# 5V_1A_Max.net
KiCad netlist of a schematic drawn in Altium Designer
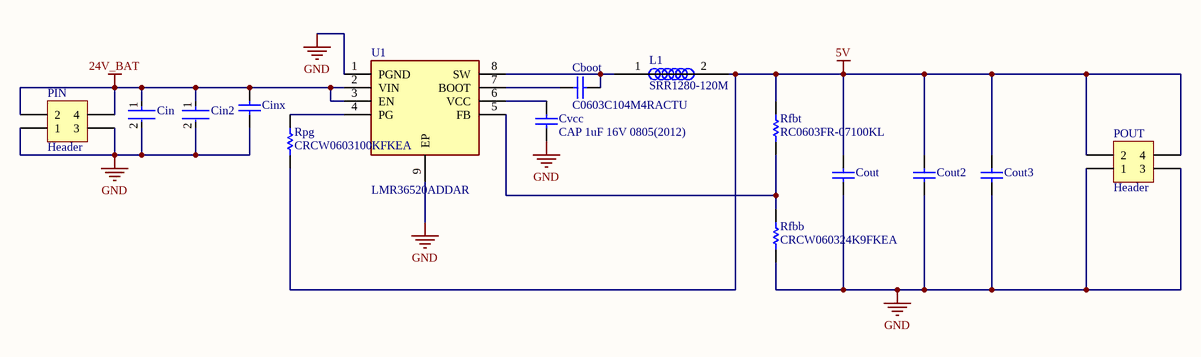
[diagram p0: 5V_1A_Max.SchDoc]

(export (version "E")
  (design (tool "Eeschema 10.0.6"))
  (components
    (comp (ref "Cboot")
      (value "C0603C104M4RACTU")
      (footprint "CAPC1608X87X35ML15T15")
      (fields (field (name "MANUFACTURER") "Kemet"))
      (libsource (lib "Altium Content Vault") (part "CAP"))
    )
    (comp (ref "Cin")
      (value "C2012X5R1H475K125AB")
      (footprint "FP-C2012-125-MFG")
      (description "CAP CER 4.7UF 50V X5R 0805")
      (fields
        (field (name "TOLERANCE") "10%")
        (field (name "OCTOPART") "https://octopart.com/c2012x5r1h475k125ab-tdk-25947720")
      )
      (libsource (lib "Altium Content Vault") (part "11868f565c42a9108669ba33697ecf6"))
    )
    (comp (ref "Cin2")
      (value "C2012X5R1H475K125AB")
      (footprint "FP-C2012-125-MFG")
      (description "CAP CER 4.7UF 50V X5R 0805")
      (fields
        (field (name "TOLERANCE") "10%")
        (field (name "OCTOPART") "https://octopart.com/c2012x5r1h475k125ab-tdk-25947720")
      )
      (libsource (lib "Altium Content Vault") (part "11868f565c42a9108669ba33697ecf6"))
    )
    (comp (ref "Cinx")
      (value "GRM21BR71H224MA01L")
      (footprint "CAPC2013X135X45ML10T25")
      (fields (field (name "MANUFACTURER") "Murata"))
      (libsource (lib "Altium Content Vault") (part "CAP"))
    )
    (comp (ref "Cout")
      (value "GRM32ER61C476KE15L")
      (footprint "MURA-1210_H_2.7_L")
      (description "Cap Ceramic, 47 uF, +/- 10%, -55 to 85 degC, 2-Pin SMD (1210), RoHS, Tape and Reel")
      (fields (field (name "TOLERANCE") "±10%") (field (name "MANUFACTURER") "Murata"))
      (libsource (lib "Altium Content Vault") (part "CAP-NP-2"))
    )
    (comp (ref "Cout2")
      (value "GRM32ER61C476KE15L")
      (footprint "MURA-1210_H_2.7_L")
      (description "Cap Ceramic, 47 uF, +/- 10%, -55 to 85 degC, 2-Pin SMD (1210), RoHS, Tape and Reel")
      (fields (field (name "TOLERANCE") "±10%") (field (name "MANUFACTURER") "Murata"))
      (libsource (lib "Altium Content Vault") (part "CAP-NP-2"))
    )
    (comp (ref "Cout3")
      (value "GRM32ER61C476KE15L")
      (footprint "MURA-1210_H_2.7_L")
      (description "Cap Ceramic, 47 uF, +/- 10%, -55 to 85 degC, 2-Pin SMD (1210), RoHS, Tape and Reel")
      (fields (field (name "TOLERANCE") "±10%") (field (name "MANUFACTURER") "Murata"))
      (libsource (lib "Altium Content Vault") (part "CAP-NP-2"))
    )
    (comp (ref "Cvcc")
      (value "CAP 1uF 16V 0805(2012)")
      (footprint "CAPC0805(2012)100_N")
      (description "CAP 1uF 16V ±10% 0805 (2012 Metric) Thickness 1mm SMD")
      (fields (field (name "TOLERANCE") "Â±10%"))
      (libsource (lib "Altium Content Vault") (part "CAP"))
    )
    (comp (ref "L1")
      (value "SRR1280-120M")
      (footprint "SRR1280-120M")
      (libsource (lib "Components") (part "SRR1280-120M"))
    )
    (comp (ref "PIN")
      (value "Header")
      (footprint "MINIFITJR 2X2")
      (description "Header, 2x2")
      (libsource (lib "Components") (part "MiniFit Jr 2x2"))
    )
    (comp (ref "POUT")
      (value "Header")
      (footprint "MINIFITJR 2X2")
      (description "Header, 2x2")
      (libsource (lib "Components") (part "MiniFit Jr 2x2"))
    )
    (comp (ref "Rfbb")
      (value "CRCW060324K9FKEA")
      (footprint "RESC1609X50X30NL10T20")
      (fields (field (name "MANUFACTURER") "Vishay Dale"))
      (libsource (lib "Altium Content Vault") (part "RES"))
    )
    (comp (ref "Rfbt")
      (value "RC0603FR-07100KL")
      (footprint "RESC1608X55X25ML10T15")
      (description "Chip Resistor, 100 KOhm, +/- 1%, 0.1 W, -55 to 155 degC, 0603 (1608 Metric), RoHS, Tape and Reel")
      (fields (field (name "MANUFACTURER") "Yageo") (field (name "TOLERANCE") "1%"))
      (libsource (lib "Altium Content Vault") (part "RES-2"))
    )
    (comp (ref "Rpg")
      (value "CRCW0603100KFKEA")
      (footprint "RESC1609X50X30LL10T20")
      (fields (field (name "MANUFACTURER") "Vishay Dale"))
      (libsource (lib "Altium Content Vault") (part "RES"))
    )
    (comp (ref "U1")
      (value "LMR36520ADDAR")
      (footprint "SamacSys:SOIC127P600X170-9N")
      (description "Integrated Circuit")
      (fields (field (name "MOUSER PART NUMBER") "595-LMR36520ADDAR"))
      (libsource (lib "*") (part "LMR36520ADDAR"))
    )
  )
  (nets
    (net (code "1") (name "5V") (class "Default")
      (node (ref "Cout") (pin "2") (pinfunction "2_2") (pintype "passive"))
      (node (ref "Cout2") (pin "2") (pinfunction "2_2") (pintype "passive"))
      (node (ref "Cout3") (pin "2") (pinfunction "2_2") (pintype "passive"))
      (node (ref "L1") (pin "2") (pinfunction "5_2") (pintype "passive"))
      (node (ref "POUT") (pin "2") (pinfunction "2_2") (pintype "passive"))
      (node (ref "POUT") (pin "4") (pinfunction "4_4") (pintype "passive"))
      (node (ref "Rfbt") (pin "2") (pinfunction "2_2") (pintype "passive"))
      (node (ref "Rpg") (pin "1") (pinfunction "1_1") (pintype "passive"))
    )
    (net (code "2") (name "24V_BAT") (class "Default")
      (node (ref "Cin") (pin "1") (pinfunction "1_1") (pintype "passive"))
      (node (ref "Cin2") (pin "1") (pinfunction "1_1") (pintype "passive"))
      (node (ref "Cinx") (pin "2") (pinfunction "2_2") (pintype "passive"))
      (node (ref "PIN") (pin "2") (pinfunction "2_2") (pintype "passive"))
      (node (ref "PIN") (pin "4") (pinfunction "4_4") (pintype "passive"))
      (node (ref "U1") (pin "2") (pinfunction "VIN_2") (pintype "passive"))
      (node (ref "U1") (pin "3") (pinfunction "EN_3") (pintype "passive"))
    )
    (net (code "3") (name "GND") (class "Default")
      (node (ref "Cin") (pin "2") (pinfunction "2_2") (pintype "passive"))
      (node (ref "Cin2") (pin "2") (pinfunction "2_2") (pintype "passive"))
      (node (ref "Cinx") (pin "1") (pinfunction "1_1") (pintype "passive"))
      (node (ref "Cout") (pin "1") (pinfunction "1_1") (pintype "passive"))
      (node (ref "Cout2") (pin "1") (pinfunction "1_1") (pintype "passive"))
      (node (ref "Cout3") (pin "1") (pinfunction "1_1") (pintype "passive"))
      (node (ref "Cvcc") (pin "1") (pinfunction "1_1") (pintype "passive"))
      (node (ref "PIN") (pin "1") (pinfunction "1_1") (pintype "passive"))
      (node (ref "PIN") (pin "3") (pinfunction "3_3") (pintype "passive"))
      (node (ref "POUT") (pin "1") (pinfunction "1_1") (pintype "passive"))
      (node (ref "POUT") (pin "3") (pinfunction "3_3") (pintype "passive"))
      (node (ref "Rfbb") (pin "1") (pinfunction "1_1") (pintype "passive"))
      (node (ref "U1") (pin "1") (pinfunction "PGND_1") (pintype "passive"))
      (node (ref "U1") (pin "9") (pinfunction "EP_9") (pintype "passive"))
    )
    (net (code "4") (name "Net-(U1-BOOT)") (class "Default")
      (node (ref "Cboot") (pin "1") (pinfunction "1_1") (pintype "passive"))
      (node (ref "U1") (pin "7") (pinfunction "BOOT_7") (pintype "passive"))
    )
    (net (code "5") (name "Net-(U1-FB)") (class "Default")
      (node (ref "Rfbb") (pin "2") (pinfunction "2_2") (pintype "passive"))
      (node (ref "Rfbt") (pin "1") (pinfunction "1_1") (pintype "passive"))
      (node (ref "U1") (pin "5") (pinfunction "FB_5") (pintype "passive"))
    )
    (net (code "6") (name "Net-(U1-PG)") (class "Default")
      (node (ref "Rpg") (pin "2") (pinfunction "2_2") (pintype "passive"))
      (node (ref "U1") (pin "4") (pinfunction "PG_4") (pintype "passive"))
    )
    (net (code "7") (name "Net-(U1-SW)") (class "Default")
      (node (ref "Cboot") (pin "2") (pinfunction "2_2") (pintype "passive"))
      (node (ref "L1") (pin "1") (pinfunction "5_1") (pintype "passive"))
      (node (ref "U1") (pin "8") (pinfunction "SW_8") (pintype "passive"))
    )
    (net (code "8") (name "Net-(U1-VCC)") (class "Default")
      (node (ref "Cvcc") (pin "2") (pinfunction "2_2") (pintype "passive"))
      (node (ref "U1") (pin "6") (pinfunction "VCC_6") (pintype "passive"))
    )
  )
)
